# Mordovia_MCH_CLK.net
KiCad netlist of a schematic drawn in Altium Designer
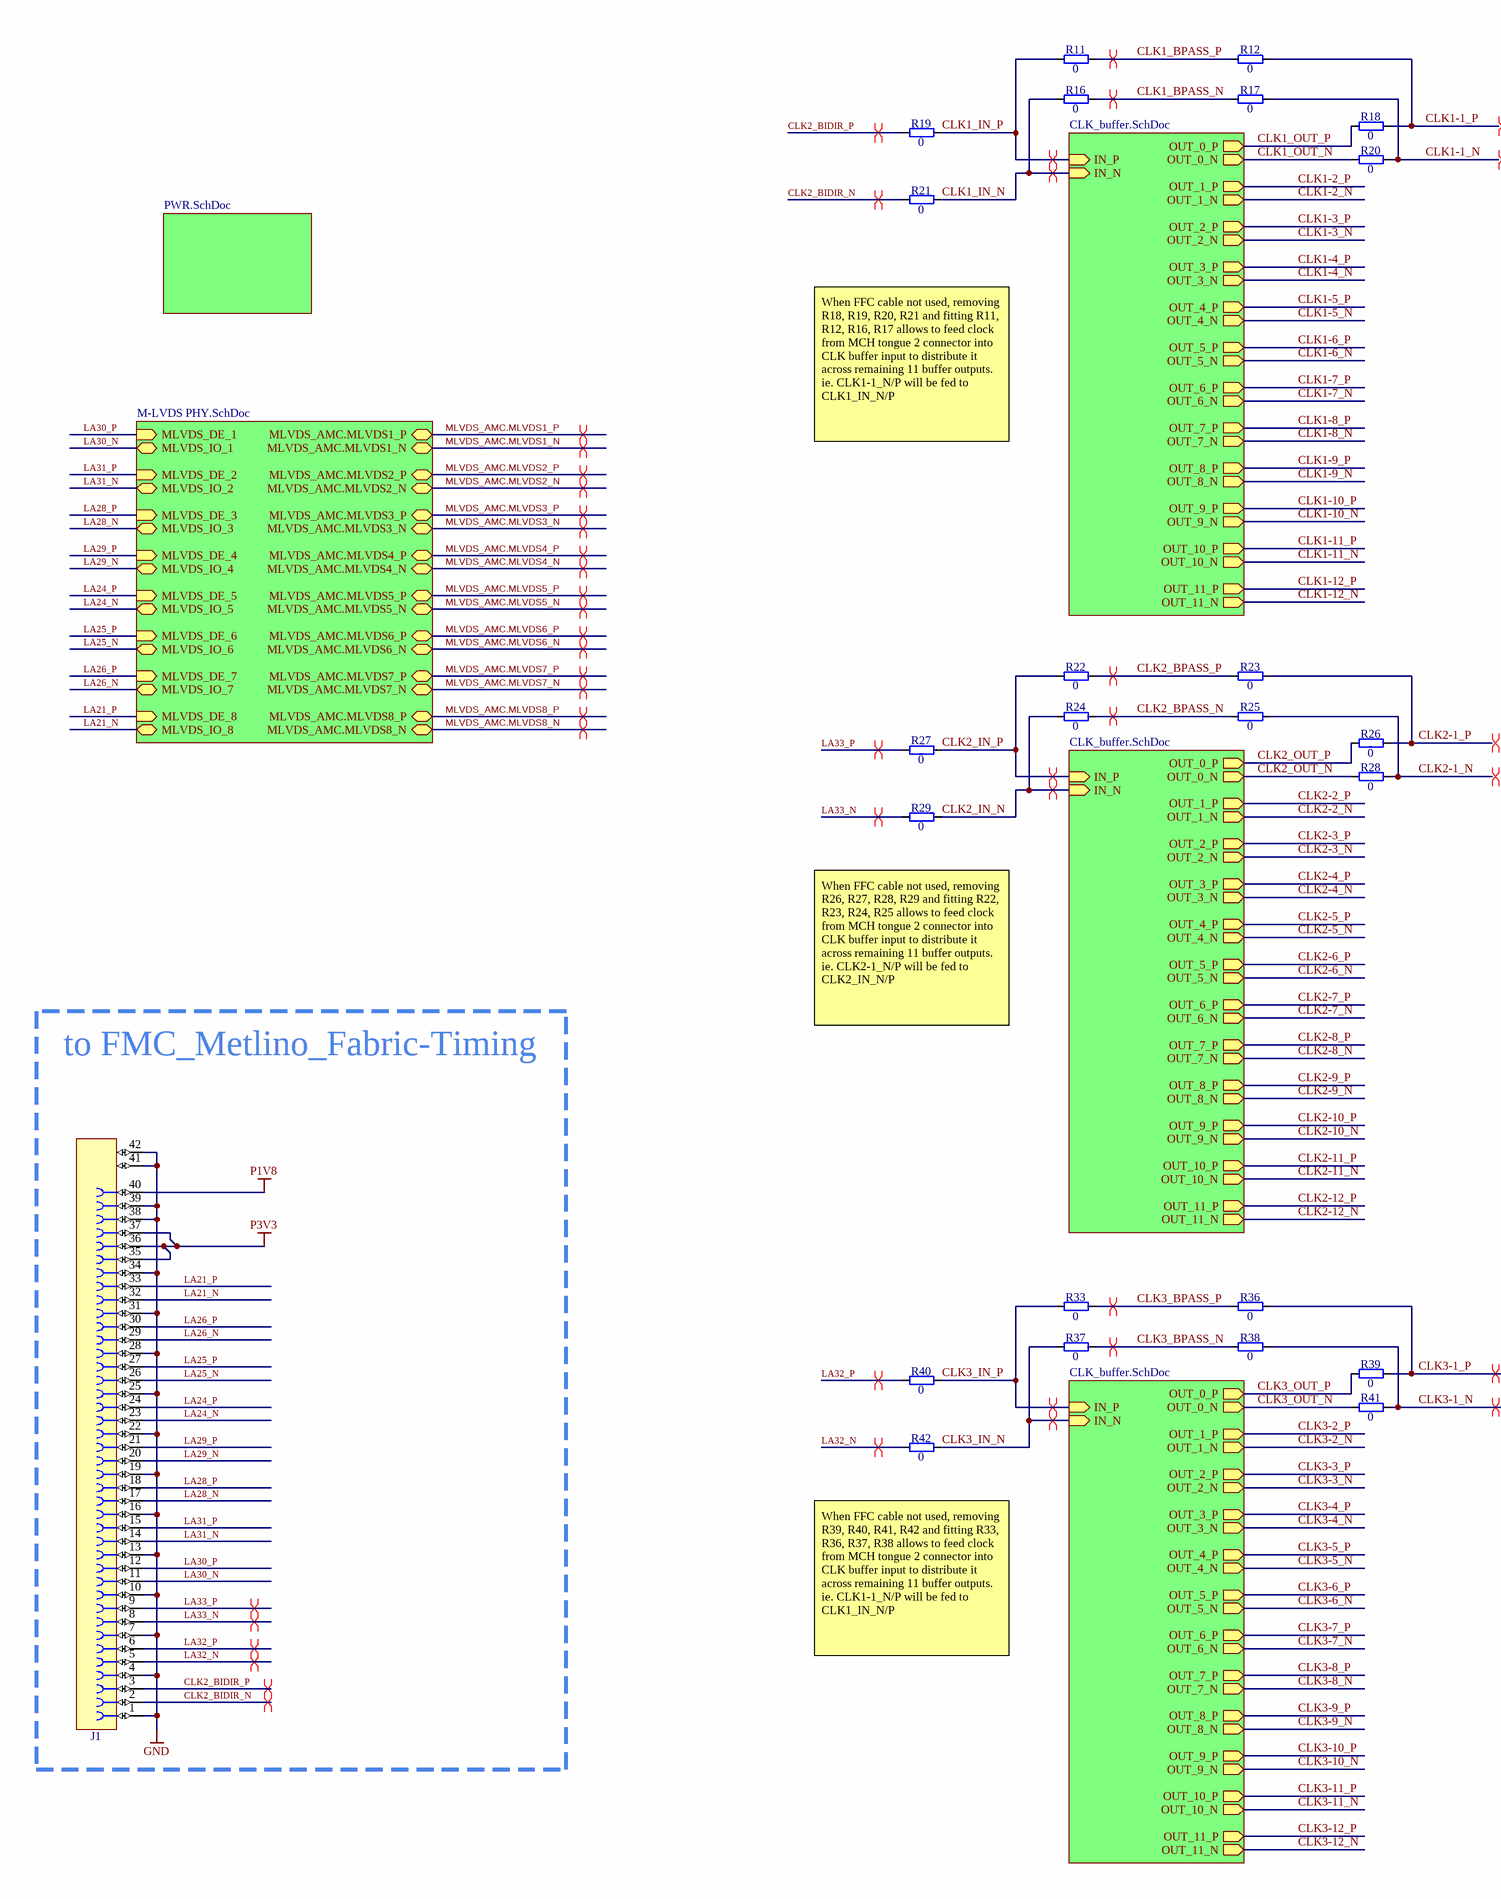
[diagram p0: Mordovia_MCH_CLK.SchDoc, left]
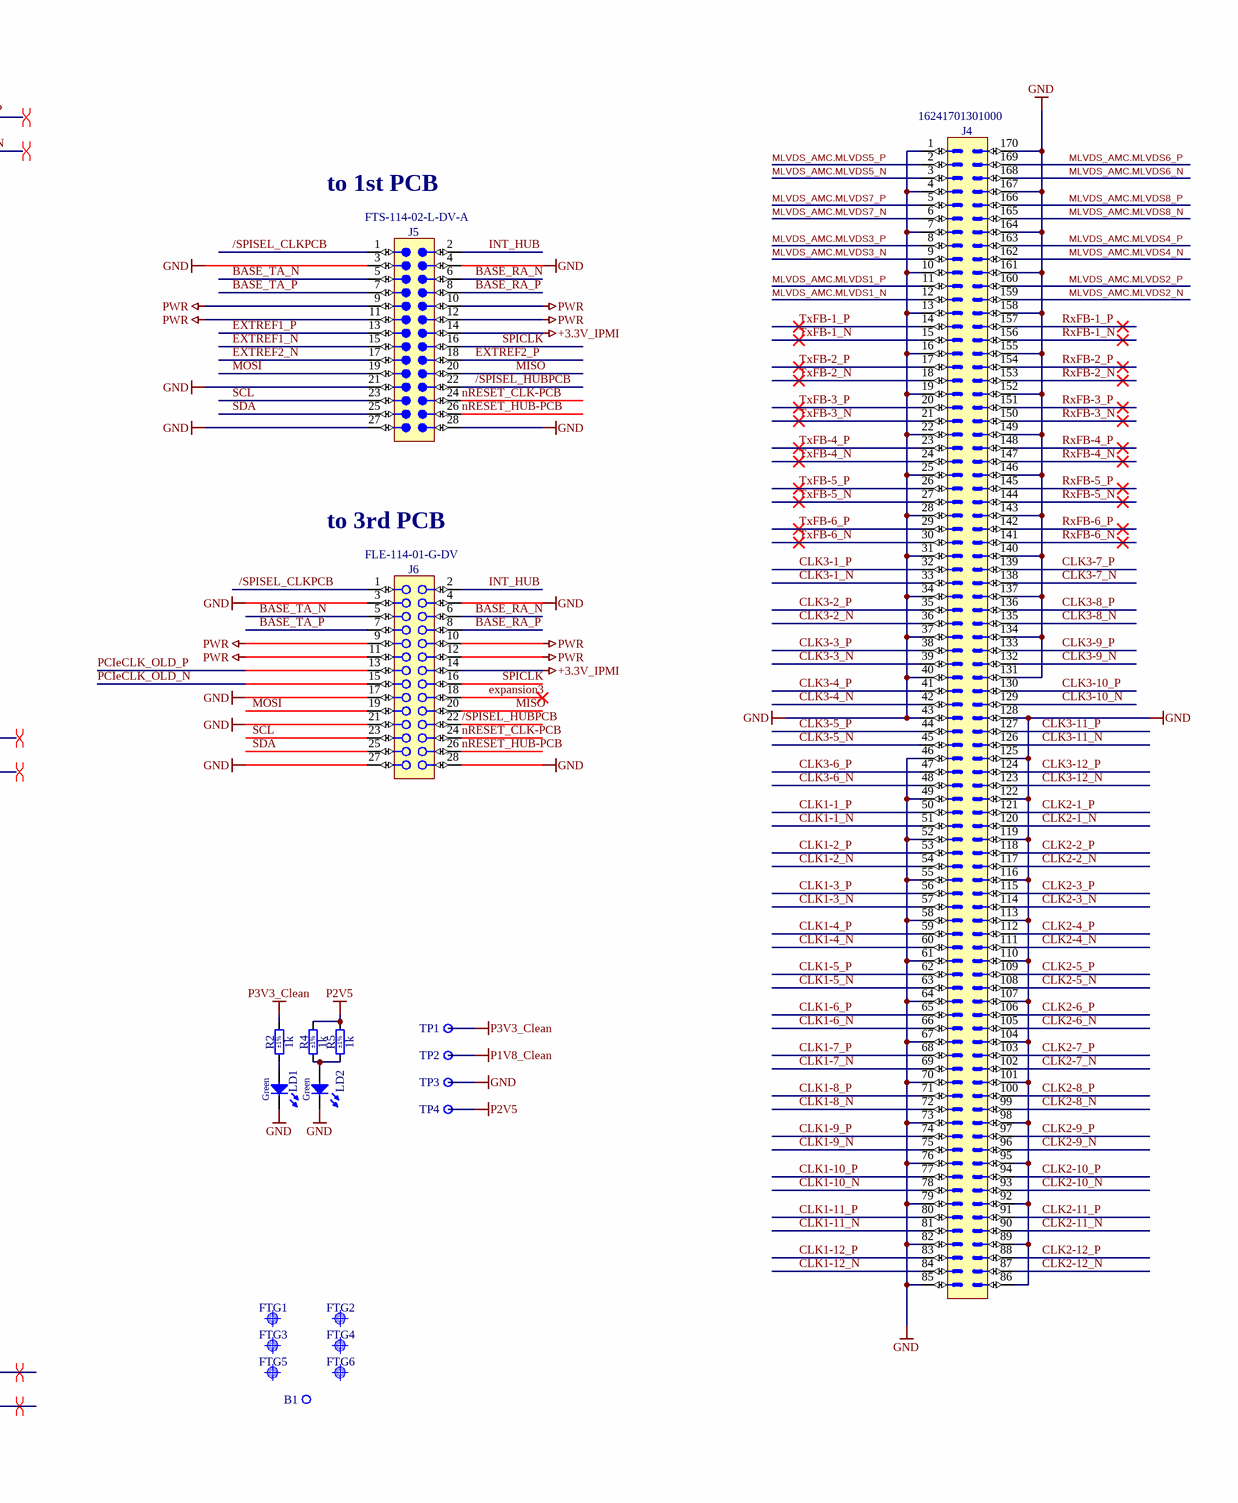
[diagram p1: Mordovia_MCH_CLK.SchDoc, right]

(export (version "E")
  (design (tool "Eeschema 10.0.6"))
  (components
    (comp (ref "B1")
      (value "Non Plated Hole")
      (footprint "MTG520")
      (description "Single Terminal Socket")
      (fields (field (name "PART NUMBER") "NON-PLATED_HOLE5.2") (field (name "AUTHOR") "CERN DEM JMW"))
      (libsource (lib "Eletro-mechanical") (part "Single Terminal Socket"))
    )
    (comp (ref "FTG1")
      (value "Use only in PCB")
      (footprint "FIDUCIAL_TOP_S100-200")
      (description "Fiducial Target")
      (fields (field (name "PART NUMBER") "FIDUCIAL_TARGET_S100-200") (field (name "AUTHOR") "CERN DEM JLC"))
      (libsource (lib "Eletro-mechanical") (part "Fiducial Target"))
    )
    (comp (ref "FTG2")
      (value "Use only in PCB")
      (footprint "FIDUCIAL_TOP_S100-200")
      (description "Fiducial Target")
      (fields (field (name "PART NUMBER") "FIDUCIAL_TARGET_S100-200") (field (name "AUTHOR") "CERN DEM JLC"))
      (libsource (lib "Eletro-mechanical") (part "Fiducial Target"))
    )
    (comp (ref "FTG3")
      (value "Use only in PCB")
      (footprint "FIDUCIAL_TOP_S100-200")
      (description "Fiducial Target")
      (fields (field (name "PART NUMBER") "FIDUCIAL_TARGET_S100-200") (field (name "AUTHOR") "CERN DEM JLC"))
      (libsource (lib "Eletro-mechanical") (part "Fiducial Target"))
    )
    (comp (ref "FTG4")
      (value "Use only in PCB")
      (footprint "FIDUCIAL_TOP_S100-200")
      (description "Fiducial Target")
      (fields (field (name "PART NUMBER") "FIDUCIAL_TARGET_S100-200") (field (name "AUTHOR") "CERN DEM JLC"))
      (libsource (lib "Eletro-mechanical") (part "Fiducial Target"))
    )
    (comp (ref "FTG5")
      (value "Use only in PCB")
      (footprint "FIDUCIAL_TOP_S100-200")
      (description "Fiducial Target")
      (fields (field (name "PART NUMBER") "FIDUCIAL_TARGET_S100-200") (field (name "AUTHOR") "CERN DEM JLC"))
      (libsource (lib "Eletro-mechanical") (part "Fiducial Target"))
    )
    (comp (ref "FTG6")
      (value "Use only in PCB")
      (footprint "FIDUCIAL_TOP_S100-200")
      (description "Fiducial Target")
      (fields (field (name "PART NUMBER") "FIDUCIAL_TARGET_S100-200") (field (name "AUTHOR") "CERN DEM JLC"))
      (libsource (lib "Eletro-mechanical") (part "Fiducial Target"))
    )
    (comp (ref "J1")
      (value "FFC/FPC")
      (footprint "MOLEX_505110-4091")
      (description "Connector 40 Female +2")
      (fields
        (field (name "PART NUMBER") "MOLEX_505110-4091")
        (field (name "MANUFACTURER") "MOLEX")
        (field (name "AUTHOR") "CERN DEM JMW")
      )
      (libsource (lib "Connectors") (part "Connector 40 Female +2"))
    )
    (comp (ref "J4")
      (value "~")
      (footprint "ITB_16241701301000")
      (description "Connector 170 Male")
      (fields
        (field (name "PART NUMBER") "ITB_16241701301000")
        (field (name "MANUFACTURER") "ITB ADVANCED CONNECTORS")
        (field (name "MANUFACTURER PART NUMBER") "16241701301000")
        (field (name "AUTHOR") "CERN DEM MR")
      )
      (libsource (lib "Connectors") (part "Connector 170 Male"))
    )
    (comp (ref "J5")
      (value "Header 28")
      (footprint "SAMTEC_FTS-114-02-L-DV-A")
      (description "Connector 28 Male")
      (fields
        (field (name "PART NUMBER") "SAMTEC_FTS-114-02-L-DV-A")
        (field (name "MANUFACTURER") "SAMTEC")
        (field (name "MANUFACTURER PART NUMBER") "FTS-114-02-L-DV-A")
        (field (name "AUTHOR") "CERN DEM MR")
      )
      (libsource (lib "Connectors") (part "Connector 28 Male"))
    )
    (comp (ref "J6")
      (value "Socket 28")
      (footprint "SAMTEC_FLE-114-01-G-DV")
      (description "Connector 28 Female")
      (fields
        (field (name "PART NUMBER") "SAMTEC_FLE-114-01-G-DV")
        (field (name "MANUFACTURER") "SAMTEC")
        (field (name "MANUFACTURER PART NUMBER") "FLE-114-01-G-DV")
        (field (name "AUTHOR") "CERN DEM MR")
      )
      (libsource (lib "Connectors") (part "Connector 28 Female"))
    )
    (comp (ref "LD1")
      (value "Green")
      (footprint "LED_OSRAM_LGL29K")
      (description "LED Green 1C 2A")
      (fields
        (field (name "PART NUMBER") "LED_OSRAM_LG L29K-G2J1-24-Z")
        (field (name "MANUFACTURER") "OSRAM")
        (field (name "AUTHOR") "CERN DEM JLC")
      )
      (libsource (lib "ICs And Semiconductors") (part "LED Green 1C 2A"))
    )
    (comp (ref "LD2")
      (value "Green")
      (footprint "LED_OSRAM_LGL29K")
      (description "LED Green 1C 2A")
      (fields
        (field (name "PART NUMBER") "LED_OSRAM_LG L29K-G2J1-24-Z")
        (field (name "MANUFACTURER") "OSRAM")
        (field (name "AUTHOR") "CERN DEM JLC")
      )
      (libsource (lib "ICs And Semiconductors") (part "LED Green 1C 2A"))
    )
    (comp (ref "R2")
      (value "1k")
      (footprint "RESC1005X40N")
      (description "Resistor - 1%")
      (fields
        (field (name "TOLERANCE") "±1%")
        (field (name "PART NUMBER") "R0402_1K_1%_0.0625W_100PPM")
        (field (name "POWER") "0.0625W")
        (field (name "AUTHOR") "CERN DEM JLC")
      )
      (libsource (lib "Resistors") (part "Resistor - 1%"))
    )
    (comp (ref "R4")
      (value "1k")
      (footprint "RESC1005X40N")
      (description "Resistor - 1%")
      (fields
        (field (name "TOLERANCE") "±1%")
        (field (name "PART NUMBER") "R0402_1K_1%_0.0625W_100PPM")
        (field (name "POWER") "0.0625W")
        (field (name "AUTHOR") "CERN DEM JLC")
      )
      (libsource (lib "Resistors") (part "Resistor - 1%"))
    )
    (comp (ref "R5")
      (value "1k")
      (footprint "RESC1005X40N")
      (description "Resistor - 1%")
      (fields
        (field (name "TOLERANCE") "±1%")
        (field (name "PART NUMBER") "R0402_1K_1%_0.0625W_100PPM")
        (field (name "POWER") "0.0625W")
        (field (name "AUTHOR") "CERN DEM JLC")
      )
      (libsource (lib "Resistors") (part "Resistor - 1%"))
    )
    (comp (ref "R11")
      (value "0")
      (footprint "RESC0603X28N")
      (description "Resistor")
      (fields
        (field (name "PART NUMBER") "R0201_0R_JUMPER")
        (field (name "MANUFACTURER") "GENERIC")
        (field (name "AUTHOR") "CERN DEM JLC")
      )
      (libsource (lib "Resistors") (part "Resistor"))
    )
    (comp (ref "R12")
      (value "0")
      (footprint "RESC0603X28N")
      (description "Resistor")
      (fields
        (field (name "PART NUMBER") "R0201_0R_JUMPER")
        (field (name "MANUFACTURER") "GENERIC")
        (field (name "AUTHOR") "CERN DEM JLC")
      )
      (libsource (lib "Resistors") (part "Resistor"))
    )
    (comp (ref "R16")
      (value "0")
      (footprint "RESC0603X28N")
      (description "Resistor")
      (fields
        (field (name "PART NUMBER") "R0201_0R_JUMPER")
        (field (name "MANUFACTURER") "GENERIC")
        (field (name "AUTHOR") "CERN DEM JLC")
      )
      (libsource (lib "Resistors") (part "Resistor"))
    )
    (comp (ref "R17")
      (value "0")
      (footprint "RESC0603X28N")
      (description "Resistor")
      (fields
        (field (name "PART NUMBER") "R0201_0R_JUMPER")
        (field (name "MANUFACTURER") "GENERIC")
        (field (name "AUTHOR") "CERN DEM JLC")
      )
      (libsource (lib "Resistors") (part "Resistor"))
    )
    (comp (ref "R18")
      (value "0")
      (footprint "RESC0603X28N")
      (description "Resistor")
      (fields
        (field (name "PART NUMBER") "R0201_0R_JUMPER")
        (field (name "MANUFACTURER") "GENERIC")
        (field (name "AUTHOR") "CERN DEM JLC")
      )
      (libsource (lib "Resistors") (part "Resistor"))
    )
    (comp (ref "R19")
      (value "0")
      (footprint "RESC0603X28N")
      (description "Resistor")
      (fields
        (field (name "PART NUMBER") "R0201_0R_JUMPER")
        (field (name "MANUFACTURER") "GENERIC")
        (field (name "AUTHOR") "CERN DEM JLC")
      )
      (libsource (lib "Resistors") (part "Resistor"))
    )
    (comp (ref "R20")
      (value "0")
      (footprint "RESC0603X28N")
      (description "Resistor")
      (fields
        (field (name "PART NUMBER") "R0201_0R_JUMPER")
        (field (name "MANUFACTURER") "GENERIC")
        (field (name "AUTHOR") "CERN DEM JLC")
      )
      (libsource (lib "Resistors") (part "Resistor"))
    )
    (comp (ref "R21")
      (value "0")
      (footprint "RESC0603X28N")
      (description "Resistor")
      (fields
        (field (name "PART NUMBER") "R0201_0R_JUMPER")
        (field (name "MANUFACTURER") "GENERIC")
        (field (name "AUTHOR") "CERN DEM JLC")
      )
      (libsource (lib "Resistors") (part "Resistor"))
    )
    (comp (ref "R22")
      (value "0")
      (footprint "RESC0603X28N")
      (description "Resistor")
      (fields
        (field (name "PART NUMBER") "R0201_0R_JUMPER")
        (field (name "MANUFACTURER") "GENERIC")
        (field (name "AUTHOR") "CERN DEM JLC")
      )
      (libsource (lib "Resistors") (part "Resistor"))
    )
    (comp (ref "R23")
      (value "0")
      (footprint "RESC0603X28N")
      (description "Resistor")
      (fields
        (field (name "PART NUMBER") "R0201_0R_JUMPER")
        (field (name "MANUFACTURER") "GENERIC")
        (field (name "AUTHOR") "CERN DEM JLC")
      )
      (libsource (lib "Resistors") (part "Resistor"))
    )
    (comp (ref "R24")
      (value "0")
      (footprint "RESC0603X28N")
      (description "Resistor")
      (fields
        (field (name "PART NUMBER") "R0201_0R_JUMPER")
        (field (name "MANUFACTURER") "GENERIC")
        (field (name "AUTHOR") "CERN DEM JLC")
      )
      (libsource (lib "Resistors") (part "Resistor"))
    )
    (comp (ref "R25")
      (value "0")
      (footprint "RESC0603X28N")
      (description "Resistor")
      (fields
        (field (name "PART NUMBER") "R0201_0R_JUMPER")
        (field (name "MANUFACTURER") "GENERIC")
        (field (name "AUTHOR") "CERN DEM JLC")
      )
      (libsource (lib "Resistors") (part "Resistor"))
    )
    (comp (ref "R26")
      (value "0")
      (footprint "RESC0603X28N")
      (description "Resistor")
      (fields
        (field (name "PART NUMBER") "R0201_0R_JUMPER")
        (field (name "MANUFACTURER") "GENERIC")
        (field (name "AUTHOR") "CERN DEM JLC")
      )
      (libsource (lib "Resistors") (part "Resistor"))
    )
    (comp (ref "R27")
      (value "0")
      (footprint "RESC0603X28N")
      (description "Resistor")
      (fields
        (field (name "PART NUMBER") "R0201_0R_JUMPER")
        (field (name "MANUFACTURER") "GENERIC")
        (field (name "AUTHOR") "CERN DEM JLC")
      )
      (libsource (lib "Resistors") (part "Resistor"))
    )
    (comp (ref "R28")
      (value "0")
      (footprint "RESC0603X28N")
      (description "Resistor")
      (fields
        (field (name "PART NUMBER") "R0201_0R_JUMPER")
        (field (name "MANUFACTURER") "GENERIC")
        (field (name "AUTHOR") "CERN DEM JLC")
      )
      (libsource (lib "Resistors") (part "Resistor"))
    )
    (comp (ref "R29")
      (value "0")
      (footprint "RESC0603X28N")
      (description "Resistor")
      (fields
        (field (name "PART NUMBER") "R0201_0R_JUMPER")
        (field (name "MANUFACTURER") "GENERIC")
        (field (name "AUTHOR") "CERN DEM JLC")
      )
      (libsource (lib "Resistors") (part "Resistor"))
    )
    (comp (ref "R33")
      (value "0")
      (footprint "RESC0603X28N")
      (description "Resistor")
      (fields
        (field (name "PART NUMBER") "R0201_0R_JUMPER")
        (field (name "MANUFACTURER") "GENERIC")
        (field (name "AUTHOR") "CERN DEM JLC")
      )
      (libsource (lib "Resistors") (part "Resistor"))
    )
    (comp (ref "R36")
      (value "0")
      (footprint "RESC0603X28N")
      (description "Resistor")
      (fields
        (field (name "PART NUMBER") "R0201_0R_JUMPER")
        (field (name "MANUFACTURER") "GENERIC")
        (field (name "AUTHOR") "CERN DEM JLC")
      )
      (libsource (lib "Resistors") (part "Resistor"))
    )
    (comp (ref "R37")
      (value "0")
      (footprint "RESC0603X28N")
      (description "Resistor")
      (fields
        (field (name "PART NUMBER") "R0201_0R_JUMPER")
        (field (name "MANUFACTURER") "GENERIC")
        (field (name "AUTHOR") "CERN DEM JLC")
      )
      (libsource (lib "Resistors") (part "Resistor"))
    )
    (comp (ref "R38")
      (value "0")
      (footprint "RESC0603X28N")
      (description "Resistor")
      (fields
        (field (name "PART NUMBER") "R0201_0R_JUMPER")
        (field (name "MANUFACTURER") "GENERIC")
        (field (name "AUTHOR") "CERN DEM JLC")
      )
      (libsource (lib "Resistors") (part "Resistor"))
    )
    (comp (ref "R39")
      (value "0")
      (footprint "RESC0603X28N")
      (description "Resistor")
      (fields
        (field (name "PART NUMBER") "R0201_0R_JUMPER")
        (field (name "MANUFACTURER") "GENERIC")
        (field (name "AUTHOR") "CERN DEM JLC")
      )
      (libsource (lib "Resistors") (part "Resistor"))
    )
    (comp (ref "R40")
      (value "0")
      (footprint "RESC0603X28N")
      (description "Resistor")
      (fields
        (field (name "PART NUMBER") "R0201_0R_JUMPER")
        (field (name "MANUFACTURER") "GENERIC")
        (field (name "AUTHOR") "CERN DEM JLC")
      )
      (libsource (lib "Resistors") (part "Resistor"))
    )
    (comp (ref "R41")
      (value "0")
      (footprint "RESC0603X28N")
      (description "Resistor")
      (fields
        (field (name "PART NUMBER") "R0201_0R_JUMPER")
        (field (name "MANUFACTURER") "GENERIC")
        (field (name "AUTHOR") "CERN DEM JLC")
      )
      (libsource (lib "Resistors") (part "Resistor"))
    )
    (comp (ref "R42")
      (value "0")
      (footprint "RESC0603X28N")
      (description "Resistor")
      (fields
        (field (name "PART NUMBER") "R0201_0R_JUMPER")
        (field (name "MANUFACTURER") "GENERIC")
        (field (name "AUTHOR") "CERN DEM JLC")
      )
      (libsource (lib "Resistors") (part "Resistor"))
    )
    (comp (ref "TP1")
      (value "Test Point")
      (footprint "TPS127")
      (fields (field (name "PART NUMBER") "SMD_PAD_1.27X1.27MM") (field (name "AUTHOR") "CERN DEM JLC"))
      (libsource (lib "Eletro-mechanical") (part "Test Point"))
    )
    (comp (ref "TP2")
      (value "Test Point")
      (footprint "TPS127")
      (fields (field (name "PART NUMBER") "SMD_PAD_1.27X1.27MM") (field (name "AUTHOR") "CERN DEM JLC"))
      (libsource (lib "Eletro-mechanical") (part "Test Point"))
    )
    (comp (ref "TP3")
      (value "Test Point")
      (footprint "TPS127")
      (fields (field (name "PART NUMBER") "SMD_PAD_1.27X1.27MM") (field (name "AUTHOR") "CERN DEM JLC"))
      (libsource (lib "Eletro-mechanical") (part "Test Point"))
    )
    (comp (ref "TP4")
      (value "Test Point")
      (footprint "TPS127")
      (fields (field (name "PART NUMBER") "SMD_PAD_1.27X1.27MM") (field (name "AUTHOR") "CERN DEM JLC"))
      (libsource (lib "Eletro-mechanical") (part "Test Point"))
    )
  )
  (nets
    (net (code "1") (name "+3.3V_IPMI") (class "Default")
      (node (ref "J5") (pin "14") (pinfunction "14_14") (pintype "bidirectional"))
      (node (ref "J6") (pin "14") (pinfunction "14_14") (pintype "bidirectional"))
    )
    (net (code "2") (name "/BASE_RA_N") (class "Default")
      (node (ref "J5") (pin "6") (pinfunction "6_6") (pintype "bidirectional"))
      (node (ref "J6") (pin "6") (pinfunction "6_6") (pintype "bidirectional"))
    )
    (net (code "3") (name "/BASE_RA_P") (class "Default")
      (node (ref "J5") (pin "8") (pinfunction "8_8") (pintype "bidirectional"))
      (node (ref "J6") (pin "8") (pinfunction "8_8") (pintype "bidirectional"))
    )
    (net (code "4") (name "/BASE_TA_N") (class "Default")
      (node (ref "J5") (pin "5") (pinfunction "5_5") (pintype "bidirectional"))
      (node (ref "J6") (pin "5") (pinfunction "5_5") (pintype "bidirectional"))
    )
    (net (code "5") (name "/BASE_TA_P") (class "Default")
      (node (ref "J5") (pin "7") (pinfunction "7_7") (pintype "bidirectional"))
      (node (ref "J6") (pin "7") (pinfunction "7_7") (pintype "bidirectional"))
    )
    (net (code "6") (name "/CLK1-1_N") (class "Default")
      (node (ref "J4") (pin "51") (pinfunction "101_51") (pintype "bidirectional"))
      (node (ref "R17") (pin "2") (pinfunction "2_2") (pintype "passive"))
      (node (ref "R20") (pin "2") (pinfunction "2_2") (pintype "passive"))
    )
    (net (code "7") (name "/CLK1-1_P") (class "Default")
      (node (ref "J4") (pin "50") (pinfunction "99_50") (pintype "bidirectional"))
      (node (ref "R12") (pin "2") (pinfunction "2_2") (pintype "passive"))
      (node (ref "R18") (pin "2") (pinfunction "2_2") (pintype "passive"))
    )
    (net (code "8") (name "/CLK1-2_N") (class "Default")
      (node (ref "J4") (pin "54") (pinfunction "107_54") (pintype "bidirectional"))
    )
    (net (code "9") (name "/CLK1-2_P") (class "Default")
      (node (ref "J4") (pin "53") (pinfunction "105_53") (pintype "bidirectional"))
    )
    (net (code "10") (name "/CLK1-3_N") (class "Default")
      (node (ref "J4") (pin "57") (pinfunction "113_57") (pintype "bidirectional"))
    )
    (net (code "11") (name "/CLK1-3_P") (class "Default")
      (node (ref "J4") (pin "56") (pinfunction "111_56") (pintype "bidirectional"))
    )
    (net (code "12") (name "/CLK1-4_N") (class "Default")
      (node (ref "J4") (pin "60") (pinfunction "119_60") (pintype "bidirectional"))
    )
    (net (code "13") (name "/CLK1-4_P") (class "Default")
      (node (ref "J4") (pin "59") (pinfunction "117_59") (pintype "bidirectional"))
    )
    (net (code "14") (name "/CLK1-5_N") (class "Default")
      (node (ref "J4") (pin "63") (pinfunction "75_63") (pintype "bidirectional"))
    )
    (net (code "15") (name "/CLK1-5_P") (class "Default")
      (node (ref "J4") (pin "62") (pinfunction "73_62") (pintype "bidirectional"))
    )
    (net (code "16") (name "/CLK1-6_N") (class "Default")
      (node (ref "J4") (pin "66") (pinfunction "81_66") (pintype "bidirectional"))
    )
    (net (code "17") (name "/CLK1-6_P") (class "Default")
      (node (ref "J4") (pin "65") (pinfunction "79_65") (pintype "bidirectional"))
    )
    (net (code "18") (name "/CLK1-7_N") (class "Default")
      (node (ref "J4") (pin "69") (pinfunction "87_69") (pintype "bidirectional"))
    )
    (net (code "19") (name "/CLK1-7_P") (class "Default")
      (node (ref "J4") (pin "68") (pinfunction "85_68") (pintype "bidirectional"))
    )
    (net (code "20") (name "/CLK1-8_N") (class "Default")
      (node (ref "J4") (pin "72") (pinfunction "93_72") (pintype "bidirectional"))
    )
    (net (code "21") (name "/CLK1-8_P") (class "Default")
      (node (ref "J4") (pin "71") (pinfunction "91_71") (pintype "bidirectional"))
    )
    (net (code "22") (name "/CLK1-9_N") (class "Default")
      (node (ref "J4") (pin "75") (pinfunction "99_75") (pintype "bidirectional"))
    )
    (net (code "23") (name "/CLK1-9_P") (class "Default")
      (node (ref "J4") (pin "74") (pinfunction "97_74") (pintype "bidirectional"))
    )
    (net (code "24") (name "/CLK1-10_N") (class "Default")
      (node (ref "J4") (pin "78") (pinfunction "105_78") (pintype "bidirectional"))
    )
    (net (code "25") (name "/CLK1-10_P") (class "Default")
      (node (ref "J4") (pin "77") (pinfunction "103_77") (pintype "bidirectional"))
    )
    (net (code "26") (name "/CLK1-11_N") (class "Default")
      (node (ref "J4") (pin "81") (pinfunction "111_81") (pintype "bidirectional"))
    )
    (net (code "27") (name "/CLK1-11_P") (class "Default")
      (node (ref "J4") (pin "80") (pinfunction "109_80") (pintype "bidirectional"))
    )
    (net (code "28") (name "/CLK1-12_N") (class "Default")
      (node (ref "J4") (pin "84") (pinfunction "117_84") (pintype "bidirectional"))
    )
    (net (code "29") (name "/CLK1-12_P") (class "Default")
      (node (ref "J4") (pin "83") (pinfunction "115_83") (pintype "bidirectional"))
    )
    (net (code "30") (name "/CLK1_BPASS_N") (class "Default")
      (node (ref "R16") (pin "2") (pinfunction "2_2") (pintype "passive"))
      (node (ref "R17") (pin "1") (pinfunction "1_1") (pintype "passive"))
    )
    (net (code "31") (name "/CLK1_BPASS_P") (class "Default")
      (node (ref "R11") (pin "2") (pinfunction "2_2") (pintype "passive"))
      (node (ref "R12") (pin "1") (pinfunction "1_1") (pintype "passive"))
    )
    (net (code "32") (name "/CLK1_IN_N") (class "Default")
      (node (ref "R16") (pin "1") (pinfunction "1_1") (pintype "passive"))
      (node (ref "R21") (pin "2") (pinfunction "2_2") (pintype "passive"))
    )
    (net (code "33") (name "/CLK1_IN_P") (class "Default")
      (node (ref "R11") (pin "1") (pinfunction "1_1") (pintype "passive"))
      (node (ref "R19") (pin "2") (pinfunction "2_2") (pintype "passive"))
    )
    (net (code "34") (name "/CLK1_OUT_N") (class "Default")
      (node (ref "R20") (pin "1") (pinfunction "1_1") (pintype "passive"))
    )
    (net (code "35") (name "/CLK1_OUT_P") (class "Default")
      (node (ref "R18") (pin "1") (pinfunction "1_1") (pintype "passive"))
    )
    (net (code "36") (name "/CLK2-1_N") (class "Default")
      (node (ref "J4") (pin "120") (pinfunction "120_120") (pintype "bidirectional"))
      (node (ref "R25") (pin "2") (pinfunction "2_2") (pintype "passive"))
      (node (ref "R28") (pin "2") (pinfunction "2_2") (pintype "passive"))
    )
    (net (code "37") (name "/CLK2-1_P") (class "Default")
      (node (ref "J4") (pin "121") (pinfunction "121_121") (pintype "bidirectional"))
      (node (ref "R23") (pin "2") (pinfunction "2_2") (pintype "passive"))
      (node (ref "R26") (pin "2") (pinfunction "2_2") (pintype "passive"))
    )
    (net (code "38") (name "/CLK2-2_N") (class "Default")
      (node (ref "J4") (pin "117") (pinfunction "117_117") (pintype "bidirectional"))
    )
    (net (code "39") (name "/CLK2-2_P") (class "Default")
      (node (ref "J4") (pin "118") (pinfunction "118_118") (pintype "bidirectional"))
    )
    (net (code "40") (name "/CLK2-3_N") (class "Default")
      (node (ref "J4") (pin "114") (pinfunction "114_114") (pintype "bidirectional"))
    )
    (net (code "41") (name "/CLK2-3_P") (class "Default")
      (node (ref "J4") (pin "115") (pinfunction "115_115") (pintype "bidirectional"))
    )
    (net (code "42") (name "/CLK2-4_N") (class "Default")
      (node (ref "J4") (pin "111") (pinfunction "111_111") (pintype "bidirectional"))
    )
    (net (code "43") (name "/CLK2-4_P") (class "Default")
      (node (ref "J4") (pin "112") (pinfunction "112_112") (pintype "bidirectional"))
    )
    (net (code "44") (name "/CLK2-5_N") (class "Default")
      (node (ref "J4") (pin "108") (pinfunction "108_108") (pintype "bidirectional"))
    )
    (net (code "45") (name "/CLK2-5_P") (class "Default")
      (node (ref "J4") (pin "109") (pinfunction "109_109") (pintype "bidirectional"))
    )
    (net (code "46") (name "/CLK2-6_N") (class "Default")
      (node (ref "J4") (pin "105") (pinfunction "105_105") (pintype "bidirectional"))
    )
    (net (code "47") (name "/CLK2-6_P") (class "Default")
      (node (ref "J4") (pin "106") (pinfunction "106_106") (pintype "bidirectional"))
    )
    (net (code "48") (name "/CLK2-7_N") (class "Default")
      (node (ref "J4") (pin "102") (pinfunction "102_102") (pintype "bidirectional"))
    )
    (net (code "49") (name "/CLK2-7_P") (class "Default")
      (node (ref "J4") (pin "103") (pinfunction "103_103") (pintype "bidirectional"))
    )
    (net (code "50") (name "/CLK2-8_N") (class "Default")
      (node (ref "J4") (pin "99") (pinfunction "99_99") (pintype "bidirectional"))
    )
    (net (code "51") (name "/CLK2-8_P") (class "Default")
      (node (ref "J4") (pin "100") (pinfunction "100_100") (pintype "bidirectional"))
    )
    (net (code "52") (name "/CLK2-9_N") (class "Default")
      (node (ref "J4") (pin "96") (pinfunction "96_96") (pintype "bidirectional"))
    )
    (net (code "53") (name "/CLK2-9_P") (class "Default")
      (node (ref "J4") (pin "97") (pinfunction "97_97") (pintype "bidirectional"))
    )
    (net (code "54") (name "/CLK2-10_N") (class "Default")
      (node (ref "J4") (pin "93") (pinfunction "93_93") (pintype "bidirectional"))
    )
    (net (code "55") (name "/CLK2-10_P") (class "Default")
      (node (ref "J4") (pin "94") (pinfunction "94_94") (pintype "bidirectional"))
    )
    (net (code "56") (name "/CLK2-11_N") (class "Default")
      (node (ref "J4") (pin "90") (pinfunction "90_90") (pintype "bidirectional"))
    )
    (net (code "57") (name "/CLK2-11_P") (class "Default")
      (node (ref "J4") (pin "91") (pinfunction "91_91") (pintype "bidirectional"))
    )
    (net (code "58") (name "/CLK2-12_N") (class "Default")
      (node (ref "J4") (pin "87") (pinfunction "87_87") (pintype "bidirectional"))
    )
    (net (code "59") (name "/CLK2-12_P") (class "Default")
      (node (ref "J4") (pin "88") (pinfunction "88_88") (pintype "bidirectional"))
    )
    (net (code "60") (name "/CLK2_BIDIR_N") (class "Default")
      (node (ref "J1") (pin "2") (pinfunction "2_2") (pintype "bidirectional"))
      (node (ref "R21") (pin "1") (pinfunction "1_1") (pintype "passive"))
    )
    (net (code "61") (name "/CLK2_BIDIR_P") (class "Default")
      (node (ref "J1") (pin "3") (pinfunction "3_3") (pintype "bidirectional"))
      (node (ref "R19") (pin "1") (pinfunction "1_1") (pintype "passive"))
    )
    (net (code "62") (name "/CLK2_BPASS_N") (class "Default")
      (node (ref "R24") (pin "2") (pinfunction "2_2") (pintype "passive"))
      (node (ref "R25") (pin "1") (pinfunction "1_1") (pintype "passive"))
    )
    (net (code "63") (name "/CLK2_BPASS_P") (class "Default")
      (node (ref "R22") (pin "2") (pinfunction "2_2") (pintype "passive"))
      (node (ref "R23") (pin "1") (pinfunction "1_1") (pintype "passive"))
    )
    (net (code "64") (name "/CLK2_IN_N") (class "Default")
      (node (ref "R24") (pin "1") (pinfunction "1_1") (pintype "passive"))
      (node (ref "R29") (pin "2") (pinfunction "2_2") (pintype "passive"))
    )
    (net (code "65") (name "/CLK2_IN_P") (class "Default")
      (node (ref "R22") (pin "1") (pinfunction "1_1") (pintype "passive"))
      (node (ref "R27") (pin "2") (pinfunction "2_2") (pintype "passive"))
    )
    (net (code "66") (name "/CLK2_OUT_N") (class "Default")
      (node (ref "R28") (pin "1") (pinfunction "1_1") (pintype "passive"))
    )
    (net (code "67") (name "/CLK2_OUT_P") (class "Default")
      (node (ref "R26") (pin "1") (pinfunction "1_1") (pintype "passive"))
    )
    (net (code "68") (name "/CLK3-1_N") (class "Default")
      (node (ref "J4") (pin "33") (pinfunction "65_33") (pintype "bidirectional"))
      (node (ref "R38") (pin "2") (pinfunction "2_2") (pintype "passive"))
      (node (ref "R41") (pin "2") (pinfunction "2_2") (pintype "passive"))
    )
    (net (code "69") (name "/CLK3-1_P") (class "Default")
      (node (ref "J4") (pin "32") (pinfunction "63_32") (pintype "bidirectional"))
      (node (ref "R36") (pin "2") (pinfunction "2_2") (pintype "passive"))
      (node (ref "R39") (pin "2") (pinfunction "2_2") (pintype "passive"))
    )
    (net (code "70") (name "/CLK3-2_N") (class "Default")
      (node (ref "J4") (pin "36") (pinfunction "71_36") (pintype "bidirectional"))
    )
    (net (code "71") (name "/CLK3-2_P") (class "Default")
      (node (ref "J4") (pin "35") (pinfunction "69_35") (pintype "bidirectional"))
    )
    (net (code "72") (name "/CLK3-3_N") (class "Default")
      (node (ref "J4") (pin "39") (pinfunction "77_39") (pintype "bidirectional"))
    )
    (net (code "73") (name "/CLK3-3_P") (class "Default")
      (node (ref "J4") (pin "38") (pinfunction "75_38") (pintype "bidirectional"))
    )
    (net (code "74") (name "/CLK3-4_N") (class "Default")
      (node (ref "J4") (pin "42") (pinfunction "83_42") (pintype "bidirectional"))
    )
    (net (code "75") (name "/CLK3-4_P") (class "Default")
      (node (ref "J4") (pin "41") (pinfunction "81_41") (pintype "bidirectional"))
    )
    (net (code "76") (name "/CLK3-5_N") (class "Default")
      (node (ref "J4") (pin "45") (pinfunction "89_45") (pintype "bidirectional"))
    )
    (net (code "77") (name "/CLK3-5_P") (class "Default")
      (node (ref "J4") (pin "44") (pinfunction "87_44") (pintype "bidirectional"))
    )
    (net (code "78") (name "/CLK3-6_N") (class "Default")
      (node (ref "J4") (pin "48") (pinfunction "95_48") (pintype "bidirectional"))
    )
    (net (code "79") (name "/CLK3-6_P") (class "Default")
      (node (ref "J4") (pin "47") (pinfunction "93_47") (pintype "bidirectional"))
    )
    (net (code "80") (name "/CLK3-7_N") (class "Default")
      (node (ref "J4") (pin "138") (pinfunction "138_138") (pintype "bidirectional"))
    )
    (net (code "81") (name "/CLK3-7_P") (class "Default")
      (node (ref "J4") (pin "139") (pinfunction "139_139") (pintype "bidirectional"))
    )
    (net (code "82") (name "/CLK3-8_N") (class "Default")
      (node (ref "J4") (pin "135") (pinfunction "135_135") (pintype "bidirectional"))
    )
    (net (code "83") (name "/CLK3-8_P") (class "Default")
      (node (ref "J4") (pin "136") (pinfunction "136_136") (pintype "bidirectional"))
    )
    (net (code "84") (name "/CLK3-9_N") (class "Default")
      (node (ref "J4") (pin "132") (pinfunction "132_132") (pintype "bidirectional"))
    )
    (net (code "85") (name "/CLK3-9_P") (class "Default")
      (node (ref "J4") (pin "133") (pinfunction "133_133") (pintype "bidirectional"))
    )
    (net (code "86") (name "/CLK3-10_N") (class "Default")
      (node (ref "J4") (pin "129") (pinfunction "129_129") (pintype "bidirectional"))
    )
    (net (code "87") (name "/CLK3-10_P") (class "Default")
      (node (ref "J4") (pin "130") (pinfunction "130_130") (pintype "bidirectional"))
    )
    (net (code "88") (name "/CLK3-11_N") (class "Default")
      (node (ref "J4") (pin "126") (pinfunction "126_126") (pintype "bidirectional"))
    )
    (net (code "89") (name "/CLK3-11_P") (class "Default")
      (node (ref "J4") (pin "127") (pinfunction "127_127") (pintype "bidirectional"))
    )
    (net (code "90") (name "/CLK3-12_N") (class "Default")
      (node (ref "J4") (pin "123") (pinfunction "123_123") (pintype "bidirectional"))
    )
    (net (code "91") (name "/CLK3-12_P") (class "Default")
      (node (ref "J4") (pin "124") (pinfunction "124_124") (pintype "bidirectional"))
    )
    (net (code "92") (name "/CLK3_BPASS_N") (class "Default")
      (node (ref "R37") (pin "2") (pinfunction "2_2") (pintype "passive"))
      (node (ref "R38") (pin "1") (pinfunction "1_1") (pintype "passive"))
    )
    (net (code "93") (name "/CLK3_BPASS_P") (class "Default")
      (node (ref "R33") (pin "2") (pinfunction "2_2") (pintype "passive"))
      (node (ref "R36") (pin "1") (pinfunction "1_1") (pintype "passive"))
    )
    (net (code "94") (name "/CLK3_IN_N") (class "Default")
      (node (ref "R37") (pin "1") (pinfunction "1_1") (pintype "passive"))
      (node (ref "R42") (pin "2") (pinfunction "2_2") (pintype "passive"))
    )
    (net (code "95") (name "/CLK3_IN_P") (class "Default")
      (node (ref "R33") (pin "1") (pinfunction "1_1") (pintype "passive"))
      (node (ref "R40") (pin "2") (pinfunction "2_2") (pintype "passive"))
    )
    (net (code "96") (name "/CLK3_OUT_N") (class "Default")
      (node (ref "R41") (pin "1") (pinfunction "1_1") (pintype "passive"))
    )
    (net (code "97") (name "/CLK3_OUT_P") (class "Default")
      (node (ref "R39") (pin "1") (pinfunction "1_1") (pintype "passive"))
    )
    (net (code "98") (name "/EXTREF1_N") (class "Default")
      (node (ref "J5") (pin "15") (pinfunction "15_15") (pintype "bidirectional"))
    )
    (net (code "99") (name "/EXTREF1_P") (class "Default")
      (node (ref "J5") (pin "13") (pinfunction "13_13") (pintype "bidirectional"))
    )
    (net (code "100") (name "/EXTREF2_N") (class "Default")
      (node (ref "J5") (pin "17") (pinfunction "17_17") (pintype "bidirectional"))
    )
    (net (code "101") (name "/EXTREF2_P") (class "Default")
      (node (ref "J5") (pin "18") (pinfunction "18_18") (pintype "bidirectional"))
    )
    (net (code "102") (name "/INT_HUB") (class "Default")
      (node (ref "J5") (pin "2") (pinfunction "2_2") (pintype "bidirectional"))
      (node (ref "J6") (pin "2") (pinfunction "2_2") (pintype "bidirectional"))
    )
    (net (code "103") (name "/LA21_N") (class "Default")
      (node (ref "J1") (pin "32") (pinfunction "32_32") (pintype "bidirectional"))
    )
    (net (code "104") (name "/LA21_P") (class "Default")
      (node (ref "J1") (pin "33") (pinfunction "33_33") (pintype "bidirectional"))
    )
    (net (code "105") (name "/LA24_N") (class "Default")
      (node (ref "J1") (pin "23") (pinfunction "23_23") (pintype "bidirectional"))
    )
    (net (code "106") (name "/LA24_P") (class "Default")
      (node (ref "J1") (pin "24") (pinfunction "24_24") (pintype "bidirectional"))
    )
    (net (code "107") (name "/LA25_N") (class "Default")
      (node (ref "J1") (pin "26") (pinfunction "26_26") (pintype "bidirectional"))
    )
    (net (code "108") (name "/LA25_P") (class "Default")
      (node (ref "J1") (pin "27") (pinfunction "27_27") (pintype "bidirectional"))
    )
    (net (code "109") (name "/LA26_N") (class "Default")
      (node (ref "J1") (pin "29") (pinfunction "29_29") (pintype "bidirectional"))
    )
    (net (code "110") (name "/LA26_P") (class "Default")
      (node (ref "J1") (pin "30") (pinfunction "30_30") (pintype "bidirectional"))
    )
    (net (code "111") (name "/LA28_N") (class "Default")
      (node (ref "J1") (pin "17") (pinfunction "17_17") (pintype "bidirectional"))
    )
    (net (code "112") (name "/LA28_P") (class "Default")
      (node (ref "J1") (pin "18") (pinfunction "18_18") (pintype "bidirectional"))
    )
    (net (code "113") (name "/LA29_N") (class "Default")
      (node (ref "J1") (pin "20") (pinfunction "20_20") (pintype "bidirectional"))
    )
    (net (code "114") (name "/LA29_P") (class "Default")
      (node (ref "J1") (pin "21") (pinfunction "21_21") (pintype "bidirectional"))
    )
    (net (code "115") (name "/LA30_N") (class "Default")
      (node (ref "J1") (pin "11") (pinfunction "11_11") (pintype "bidirectional"))
    )
    (net (code "116") (name "/LA30_P") (class "Default")
      (node (ref "J1") (pin "12") (pinfunction "12_12") (pintype "bidirectional"))
    )
    (net (code "117") (name "/LA31_N") (class "Default")
      (node (ref "J1") (pin "14") (pinfunction "14_14") (pintype "bidirectional"))
    )
    (net (code "118") (name "/LA31_P") (class "Default")
      (node (ref "J1") (pin "15") (pinfunction "15_15") (pintype "bidirectional"))
    )
    (net (code "119") (name "/LA32_N") (class "Default")
      (node (ref "J1") (pin "5") (pinfunction "5_5") (pintype "bidirectional"))
      (node (ref "R42") (pin "1") (pinfunction "1_1") (pintype "passive"))
    )
    (net (code "120") (name "/LA32_P") (class "Default")
      (node (ref "J1") (pin "6") (pinfunction "6_6") (pintype "bidirectional"))
      (node (ref "R40") (pin "1") (pinfunction "1_1") (pintype "passive"))
    )
    (net (code "121") (name "/LA33_N") (class "Default")
      (node (ref "J1") (pin "8") (pinfunction "8_8") (pintype "bidirectional"))
      (node (ref "R29") (pin "1") (pinfunction "1_1") (pintype "passive"))
    )
    (net (code "122") (name "/LA33_P") (class "Default")
      (node (ref "J1") (pin "9") (pinfunction "9_9") (pintype "bidirectional"))
      (node (ref "R27") (pin "1") (pinfunction "1_1") (pintype "passive"))
    )
    (net (code "123") (name "/MISO") (class "Default")
      (node (ref "J5") (pin "20") (pinfunction "20_20") (pintype "bidirectional"))
      (node (ref "J6") (pin "20") (pinfunction "20_20") (pintype "bidirectional"))
    )
    (net (code "124") (name "/MLVDS_AMC.MLVDS1_N") (class "Default")
      (node (ref "J4") (pin "12") (pinfunction "23_12") (pintype "bidirectional"))
    )
    (net (code "125") (name "/MLVDS_AMC.MLVDS1_P") (class "Default")
      (node (ref "J4") (pin "11") (pinfunction "21_11") (pintype "bidirectional"))
    )
    (net (code "126") (name "/MLVDS_AMC.MLVDS2_N") (class "Default")
      (node (ref "J4") (pin "159") (pinfunction "159_159") (pintype "bidirectional"))
    )
    (net (code "127") (name "/MLVDS_AMC.MLVDS2_P") (class "Default")
      (node (ref "J4") (pin "160") (pinfunction "160_160") (pintype "bidirectional"))
    )
    (net (code "128") (name "/MLVDS_AMC.MLVDS3_N") (class "Default")
      (node (ref "J4") (pin "9") (pinfunction "17_9") (pintype "bidirectional"))
    )
    (net (code "129") (name "/MLVDS_AMC.MLVDS3_P") (class "Default")
      (node (ref "J4") (pin "8") (pinfunction "15_8") (pintype "bidirectional"))
    )
    (net (code "130") (name "/MLVDS_AMC.MLVDS4_N") (class "Default")
      (node (ref "J4") (pin "162") (pinfunction "162_162") (pintype "bidirectional"))
    )
    (net (code "131") (name "/MLVDS_AMC.MLVDS4_P") (class "Default")
      (node (ref "J4") (pin "163") (pinfunction "163_163") (pintype "bidirectional"))
    )
    (net (code "132") (name "/MLVDS_AMC.MLVDS5_N") (class "Default")
      (node (ref "J4") (pin "3") (pinfunction "5_3") (pintype "bidirectional"))
    )
    (net (code "133") (name "/MLVDS_AMC.MLVDS5_P") (class "Default")
      (node (ref "J4") (pin "2") (pinfunction "3_2") (pintype "bidirectional"))
    )
    (net (code "134") (name "/MLVDS_AMC.MLVDS6_N") (class "Default")
      (node (ref "J4") (pin "168") (pinfunction "168_168") (pintype "bidirectional"))
    )
    (net (code "135") (name "/MLVDS_AMC.MLVDS6_P") (class "Default")
      (node (ref "J4") (pin "169") (pinfunction "169_169") (pintype "bidirectional"))
    )
    (net (code "136") (name "/MLVDS_AMC.MLVDS7_N") (class "Default")
      (node (ref "J4") (pin "6") (pinfunction "11_6") (pintype "bidirectional"))
    )
    (net (code "137") (name "/MLVDS_AMC.MLVDS7_P") (class "Default")
      (node (ref "J4") (pin "5") (pinfunction "9_5") (pintype "bidirectional"))
    )
    (net (code "138") (name "/MLVDS_AMC.MLVDS8_N") (class "Default")
      (node (ref "J4") (pin "165") (pinfunction "165_165") (pintype "bidirectional"))
    )
    (net (code "139") (name "/MLVDS_AMC.MLVDS8_P") (class "Default")
      (node (ref "J4") (pin "166") (pinfunction "166_166") (pintype "bidirectional"))
    )
    (net (code "140") (name "/MOSI") (class "Default")
      (node (ref "J5") (pin "19") (pinfunction "19_19") (pintype "bidirectional"))
      (node (ref "J6") (pin "19") (pinfunction "19_19") (pintype "bidirectional"))
    )
    (net (code "141") (name "/PCIeCLK_OLD_N") (class "Default")
      (node (ref "J6") (pin "15") (pinfunction "15_15") (pintype "bidirectional"))
    )
    (net (code "142") (name "/PCIeCLK_OLD_P") (class "Default")
      (node (ref "J6") (pin "13") (pinfunction "13_13") (pintype "bidirectional"))
    )
    (net (code "143") (name "/RxFB-1_N") (class "Default")
      (node (ref "J4") (pin "156") (pinfunction "156_156") (pintype "bidirectional"))
    )
    (net (code "144") (name "/RxFB-1_P") (class "Default")
      (node (ref "J4") (pin "157") (pinfunction "157_157") (pintype "bidirectional"))
    )
    (net (code "145") (name "/RxFB-2_N") (class "Default")
      (node (ref "J4") (pin "153") (pinfunction "153_153") (pintype "bidirectional"))
    )
    (net (code "146") (name "/RxFB-2_P") (class "Default")
      (node (ref "J4") (pin "154") (pinfunction "154_154") (pintype "bidirectional"))
    )
    (net (code "147") (name "/RxFB-3_N") (class "Default")
      (node (ref "J4") (pin "150") (pinfunction "150_150") (pintype "bidirectional"))
    )
    (net (code "148") (name "/RxFB-3_P") (class "Default")
      (node (ref "J4") (pin "151") (pinfunction "151_151") (pintype "bidirectional"))
    )
    (net (code "149") (name "/RxFB-4_N") (class "Default")
      (node (ref "J4") (pin "147") (pinfunction "147_147") (pintype "bidirectional"))
    )
    (net (code "150") (name "/RxFB-4_P") (class "Default")
      (node (ref "J4") (pin "148") (pinfunction "148_148") (pintype "bidirectional"))
    )
    (net (code "151") (name "/RxFB-5_N") (class "Default")
      (node (ref "J4") (pin "144") (pinfunction "144_144") (pintype "bidirectional"))
    )
    (net (code "152") (name "/RxFB-5_P") (class "Default")
      (node (ref "J4") (pin "145") (pinfunction "145_145") (pintype "bidirectional"))
    )
    (net (code "153") (name "/RxFB-6_N") (class "Default")
      (node (ref "J4") (pin "141") (pinfunction "141_141") (pintype "bidirectional"))
    )
    (net (code "154") (name "/RxFB-6_P") (class "Default")
      (node (ref "J4") (pin "142") (pinfunction "142_142") (pintype "bidirectional"))
    )
    (net (code "155") (name "/SCL") (class "Default")
      (node (ref "J5") (pin "23") (pinfunction "23_23") (pintype "bidirectional"))
      (node (ref "J6") (pin "23") (pinfunction "23_23") (pintype "bidirectional"))
    )
    (net (code "156") (name "/SDA") (class "Default")
      (node (ref "J5") (pin "25") (pinfunction "25_25") (pintype "bidirectional"))
      (node (ref "J6") (pin "25") (pinfunction "25_25") (pintype "bidirectional"))
    )
    (net (code "157") (name "/SPICLK") (class "Default")
      (node (ref "J5") (pin "16") (pinfunction "16_16") (pintype "bidirectional"))
      (node (ref "J6") (pin "16") (pinfunction "16_16") (pintype "bidirectional"))
    )
    (net (code "170") (name "/TxFB-1_N") (class "Default")
      (node (ref "J4") (pin "15") (pinfunction "29_15") (pintype "bidirectional"))
    )
    (net (code "171") (name "/TxFB-1_P") (class "Default")
      (node (ref "J4") (pin "14") (pinfunction "27_14") (pintype "bidirectional"))
    )
    (net (code "172") (name "/TxFB-2_N") (class "Default")
      (node (ref "J4") (pin "18") (pinfunction "35_18") (pintype "bidirectional"))
    )
    (net (code "173") (name "/TxFB-2_P") (class "Default")
      (node (ref "J4") (pin "17") (pinfunction "33_17") (pintype "bidirectional"))
    )
    (net (code "174") (name "/TxFB-3_N") (class "Default")
      (node (ref "J4") (pin "21") (pinfunction "41_21") (pintype "bidirectional"))
    )
    (net (code "175") (name "/TxFB-3_P") (class "Default")
      (node (ref "J4") (pin "20") (pinfunction "39_20") (pintype "bidirectional"))
    )
    (net (code "176") (name "/TxFB-4_N") (class "Default")
      (node (ref "J4") (pin "24") (pinfunction "47_24") (pintype "bidirectional"))
    )
    (net (code "177") (name "/TxFB-4_P") (class "Default")
      (node (ref "J4") (pin "23") (pinfunction "45_23") (pintype "bidirectional"))
    )
    (net (code "178") (name "/TxFB-5_N") (class "Default")
      (node (ref "J4") (pin "27") (pinfunction "53_27") (pintype "bidirectional"))
    )
    (net (code "179") (name "/TxFB-5_P") (class "Default")
      (node (ref "J4") (pin "26") (pinfunction "51_26") (pintype "bidirectional"))
    )
    (net (code "180") (name "/TxFB-6_N") (class "Default")
      (node (ref "J4") (pin "30") (pinfunction "59_30") (pintype "bidirectional"))
    )
    (net (code "181") (name "/TxFB-6_P") (class "Default")
      (node (ref "J4") (pin "29") (pinfunction "57_29") (pintype "bidirectional"))
    )
    (net (code "182") (name "/expansion3") (class "Default")
      (node (ref "J6") (pin "18") (pinfunction "18_18") (pintype "bidirectional+no_connect"))
    )
    (net (code "183") (name "/nRESET_CLK-PCB") (class "Default")
      (node (ref "J5") (pin "24") (pinfunction "24_24") (pintype "bidirectional"))
      (node (ref "J6") (pin "24") (pinfunction "24_24") (pintype "bidirectional"))
    )
    (net (code "184") (name "/nRESET_HUB-PCB") (class "Default")
      (node (ref "J5") (pin "26") (pinfunction "26_26") (pintype "bidirectional"))
      (node (ref "J6") (pin "26") (pinfunction "26_26") (pintype "bidirectional"))
    )
    (net (code "185") (name "/{slash}SPISEL_CLKPCB") (class "Default")
      (node (ref "J5") (pin "1") (pinfunction "1_1") (pintype "bidirectional"))
      (node (ref "J6") (pin "1") (pinfunction "1_1") (pintype "bidirectional"))
    )
    (net (code "186") (name "/{slash}SPISEL_HUBPCB") (class "Default")
      (node (ref "J5") (pin "22") (pinfunction "22_22") (pintype "bidirectional"))
      (node (ref "J6") (pin "22") (pinfunction "22_22") (pintype "bidirectional"))
    )
    (net (code "187") (name "GND") (class "Default")
      (node (ref "J1") (pin "1") (pinfunction "1_1") (pintype "bidirectional"))
      (node (ref "J1") (pin "10") (pinfunction "10_10") (pintype "bidirectional"))
      (node (ref "J1") (pin "13") (pinfunction "13_13") (pintype "bidirectional"))
      (node (ref "J1") (pin "16") (pinfunction "16_16") (pintype "bidirectional"))
      (node (ref "J1") (pin "19") (pinfunction "19_19") (pintype "bidirectional"))
      (node (ref "J1") (pin "22") (pinfunction "22_22") (pintype "bidirectional"))
      (node (ref "J1") (pin "25") (pinfunction "25_25") (pintype "bidirectional"))
      (node (ref "J1") (pin "28") (pinfunction "28_28") (pintype "bidirectional"))
      (node (ref "J1") (pin "31") (pinfunction "31_31") (pintype "bidirectional"))
      (node (ref "J1") (pin "34") (pinfunction "34_34") (pintype "bidirectional"))
      (node (ref "J1") (pin "38") (pinfunction "38_38") (pintype "bidirectional"))
      (node (ref "J1") (pin "39") (pinfunction "39_39") (pintype "bidirectional"))
      (node (ref "J1") (pin "4") (pinfunction "4_4") (pintype "bidirectional"))
      (node (ref "J1") (pin "41") (pinfunction "41_41") (pintype "bidirectional"))
      (node (ref "J1") (pin "42") (pinfunction "42_42") (pintype "bidirectional"))
      (node (ref "J1") (pin "7") (pinfunction "7_7") (pintype "bidirectional"))
      (node (ref "J4") (pin "1") (pinfunction "1_1") (pintype "bidirectional"))
      (node (ref "J4") (pin "10") (pinfunction "19_10") (pintype "bidirectional"))
      (node (ref "J4") (pin "101") (pinfunction "101_101") (pintype "bidirectional"))
      (node (ref "J4") (pin "104") (pinfunction "104_104") (pintype "bidirectional"))
      (node (ref "J4") (pin "107") (pinfunction "107_107") (pintype "bidirectional"))
      (node (ref "J4") (pin "110") (pinfunction "110_110") (pintype "bidirectional"))
      (node (ref "J4") (pin "113") (pinfunction "113_113") (pintype "bidirectional"))
      (node (ref "J4") (pin "116") (pinfunction "116_116") (pintype "bidirectional"))
      (node (ref "J4") (pin "119") (pinfunction "119_119") (pintype "bidirectional"))
      (node (ref "J4") (pin "122") (pinfunction "122_122") (pintype "bidirectional"))
      (node (ref "J4") (pin "125") (pinfunction "125_125") (pintype "bidirectional"))
      (node (ref "J4") (pin "128") (pinfunction "128_128") (pintype "bidirectional"))
      (node (ref "J4") (pin "13") (pinfunction "25_13") (pintype "bidirectional"))
      (node (ref "J4") (pin "131") (pinfunction "131_131") (pintype "bidirectional"))
      (node (ref "J4") (pin "134") (pinfunction "134_134") (pintype "bidirectional"))
      (node (ref "J4") (pin "137") (pinfunction "137_137") (pintype "bidirectional"))
      (node (ref "J4") (pin "140") (pinfunction "140_140") (pintype "bidirectional"))
      (node (ref "J4") (pin "143") (pinfunction "143_143") (pintype "bidirectional"))
      (node (ref "J4") (pin "146") (pinfunction "146_146") (pintype "bidirectional"))
      (node (ref "J4") (pin "149") (pinfunction "149_149") (pintype "bidirectional"))
      (node (ref "J4") (pin "152") (pinfunction "152_152") (pintype "bidirectional"))
      (node (ref "J4") (pin "155") (pinfunction "155_155") (pintype "bidirectional"))
      (node (ref "J4") (pin "158") (pinfunction "158_158") (pintype "bidirectional"))
      (node (ref "J4") (pin "16") (pinfunction "31_16") (pintype "bidirectional"))
      (node (ref "J4") (pin "161") (pinfunction "161_161") (pintype "bidirectional"))
      (node (ref "J4") (pin "164") (pinfunction "164_164") (pintype "bidirectional"))
      (node (ref "J4") (pin "167") (pinfunction "167_167") (pintype "bidirectional"))
      (node (ref "J4") (pin "170") (pinfunction "170_170") (pintype "bidirectional"))
      (node (ref "J4") (pin "19") (pinfunction "37_19") (pintype "bidirectional"))
      (node (ref "J4") (pin "22") (pinfunction "43_22") (pintype "bidirectional"))
      (node (ref "J4") (pin "25") (pinfunction "49_25") (pintype "bidirectional"))
      (node (ref "J4") (pin "28") (pinfunction "55_28") (pintype "bidirectional"))
      (node (ref "J4") (pin "31") (pinfunction "61_31") (pintype "bidirectional"))
      (node (ref "J4") (pin "34") (pinfunction "67_34") (pintype "bidirectional"))
      (node (ref "J4") (pin "37") (pinfunction "73_37") (pintype "bidirectional"))
      (node (ref "J4") (pin "4") (pinfunction "7_4") (pintype "bidirectional"))
      (node (ref "J4") (pin "40") (pinfunction "79_40") (pintype "bidirectional"))
      (node (ref "J4") (pin "43") (pinfunction "85_43") (pintype "bidirectional"))
      (node (ref "J4") (pin "46") (pinfunction "91_46") (pintype "bidirectional"))
      (node (ref "J4") (pin "49") (pinfunction "97_49") (pintype "bidirectional"))
      (node (ref "J4") (pin "52") (pinfunction "103_52") (pintype "bidirectional"))
      (node (ref "J4") (pin "55") (pinfunction "109_55") (pintype "bidirectional"))
      (node (ref "J4") (pin "58") (pinfunction "115_58") (pintype "bidirectional"))
      (node (ref "J4") (pin "61") (pinfunction "71_61") (pintype "bidirectional"))
      (node (ref "J4") (pin "64") (pinfunction "77_64") (pintype "bidirectional"))
      (node (ref "J4") (pin "67") (pinfunction "83_67") (pintype "bidirectional"))
      (node (ref "J4") (pin "7") (pinfunction "13_7") (pintype "bidirectional"))
      (node (ref "J4") (pin "70") (pinfunction "89_70") (pintype "bidirectional"))
      (node (ref "J4") (pin "73") (pinfunction "95_73") (pintype "bidirectional"))
      (node (ref "J4") (pin "76") (pinfunction "101_76") (pintype "bidirectional"))
      (node (ref "J4") (pin "79") (pinfunction "107_79") (pintype "bidirectional"))
      (node (ref "J4") (pin "82") (pinfunction "113_82") (pintype "bidirectional"))
      (node (ref "J4") (pin "85") (pinfunction "119_85") (pintype "bidirectional"))
      (node (ref "J4") (pin "86") (pinfunction "86_86") (pintype "bidirectional"))
      (node (ref "J4") (pin "89") (pinfunction "89_89") (pintype "bidirectional"))
      (node (ref "J4") (pin "92") (pinfunction "92_92") (pintype "bidirectional"))
      (node (ref "J4") (pin "95") (pinfunction "95_95") (pintype "bidirectional"))
      (node (ref "J4") (pin "98") (pinfunction "98_98") (pintype "bidirectional"))
      (node (ref "J5") (pin "21") (pinfunction "21_21") (pintype "bidirectional"))
      (node (ref "J5") (pin "27") (pinfunction "27_27") (pintype "bidirectional"))
      (node (ref "J5") (pin "28") (pinfunction "28_28") (pintype "bidirectional"))
      (node (ref "J5") (pin "3") (pinfunction "3_3") (pintype "bidirectional"))
      (node (ref "J5") (pin "4") (pinfunction "4_4") (pintype "bidirectional"))
      (node (ref "J6") (pin "17") (pinfunction "17_17") (pintype "bidirectional"))
      (node (ref "J6") (pin "21") (pinfunction "21_21") (pintype "bidirectional"))
      (node (ref "J6") (pin "27") (pinfunction "27_27") (pintype "bidirectional"))
      (node (ref "J6") (pin "28") (pinfunction "28_28") (pintype "bidirectional"))
      (node (ref "J6") (pin "3") (pinfunction "3_3") (pintype "bidirectional"))
      (node (ref "J6") (pin "4") (pinfunction "4_4") (pintype "bidirectional"))
      (node (ref "LD1") (pin "1") (pinfunction "C_1") (pintype "passive"))
      (node (ref "LD2") (pin "1") (pinfunction "C_1") (pintype "passive"))
      (node (ref "TP3") (pin "1") (pinfunction "1_1") (pintype "bidirectional"))
    )
    (net (code "188") (name "Net-(LD1-A)") (class "Default")
      (node (ref "LD1") (pin "2") (pinfunction "A_2") (pintype "passive"))
      (node (ref "R2") (pin "1") (pinfunction "1_1") (pintype "passive"))
    )
    (net (code "189") (name "Net-(LD2-A)") (class "Default")
      (node (ref "LD2") (pin "2") (pinfunction "A_2") (pintype "passive"))
      (node (ref "R4") (pin "1") (pinfunction "1_1") (pintype "passive"))
      (node (ref "R5") (pin "1") (pinfunction "1_1") (pintype "passive"))
    )
    (net (code "190") (name "P1V8") (class "Default")
      (node (ref "J1") (pin "40") (pinfunction "40_40") (pintype "bidirectional"))
    )
    (net (code "191") (name "P1V8_Clean") (class "Default")
      (node (ref "TP2") (pin "1") (pinfunction "1_1") (pintype "bidirectional"))
    )
    (net (code "192") (name "P2V5") (class "Default")
      (node (ref "R4") (pin "2") (pinfunction "2_2") (pintype "passive"))
      (node (ref "R5") (pin "2") (pinfunction "2_2") (pintype "passive"))
      (node (ref "TP4") (pin "1") (pinfunction "1_1") (pintype "bidirectional"))
    )
    (net (code "193") (name "P3V3") (class "Default")
      (node (ref "J1") (pin "35") (pinfunction "35_35") (pintype "bidirectional"))
      (node (ref "J1") (pin "36") (pinfunction "36_36") (pintype "bidirectional"))
      (node (ref "J1") (pin "37") (pinfunction "37_37") (pintype "bidirectional"))
    )
    (net (code "194") (name "P3V3_Clean") (class "Default")
      (node (ref "R2") (pin "2") (pinfunction "2_2") (pintype "passive"))
      (node (ref "TP1") (pin "1") (pinfunction "1_1") (pintype "bidirectional"))
    )
    (net (code "195") (name "PWR") (class "Default")
      (node (ref "J5") (pin "10") (pinfunction "10_10") (pintype "bidirectional"))
      (node (ref "J5") (pin "11") (pinfunction "11_11") (pintype "bidirectional"))
      (node (ref "J5") (pin "12") (pinfunction "12_12") (pintype "bidirectional"))
      (node (ref "J5") (pin "9") (pinfunction "9_9") (pintype "bidirectional"))
      (node (ref "J6") (pin "10") (pinfunction "10_10") (pintype "bidirectional"))
      (node (ref "J6") (pin "11") (pinfunction "11_11") (pintype "bidirectional"))
      (node (ref "J6") (pin "12") (pinfunction "12_12") (pintype "bidirectional"))
      (node (ref "J6") (pin "9") (pinfunction "9_9") (pintype "bidirectional"))
    )
    (net (code "196") (name "unconnected-(B1-Pad1)") (class "Default")
      (node (ref "B1") (pin "1") (pinfunction "1_1") (pintype "bidirectional"))
    )
  )
)
